# arduinoVisor2.net
KiCad netlist of a schematic drawn in EAGLE
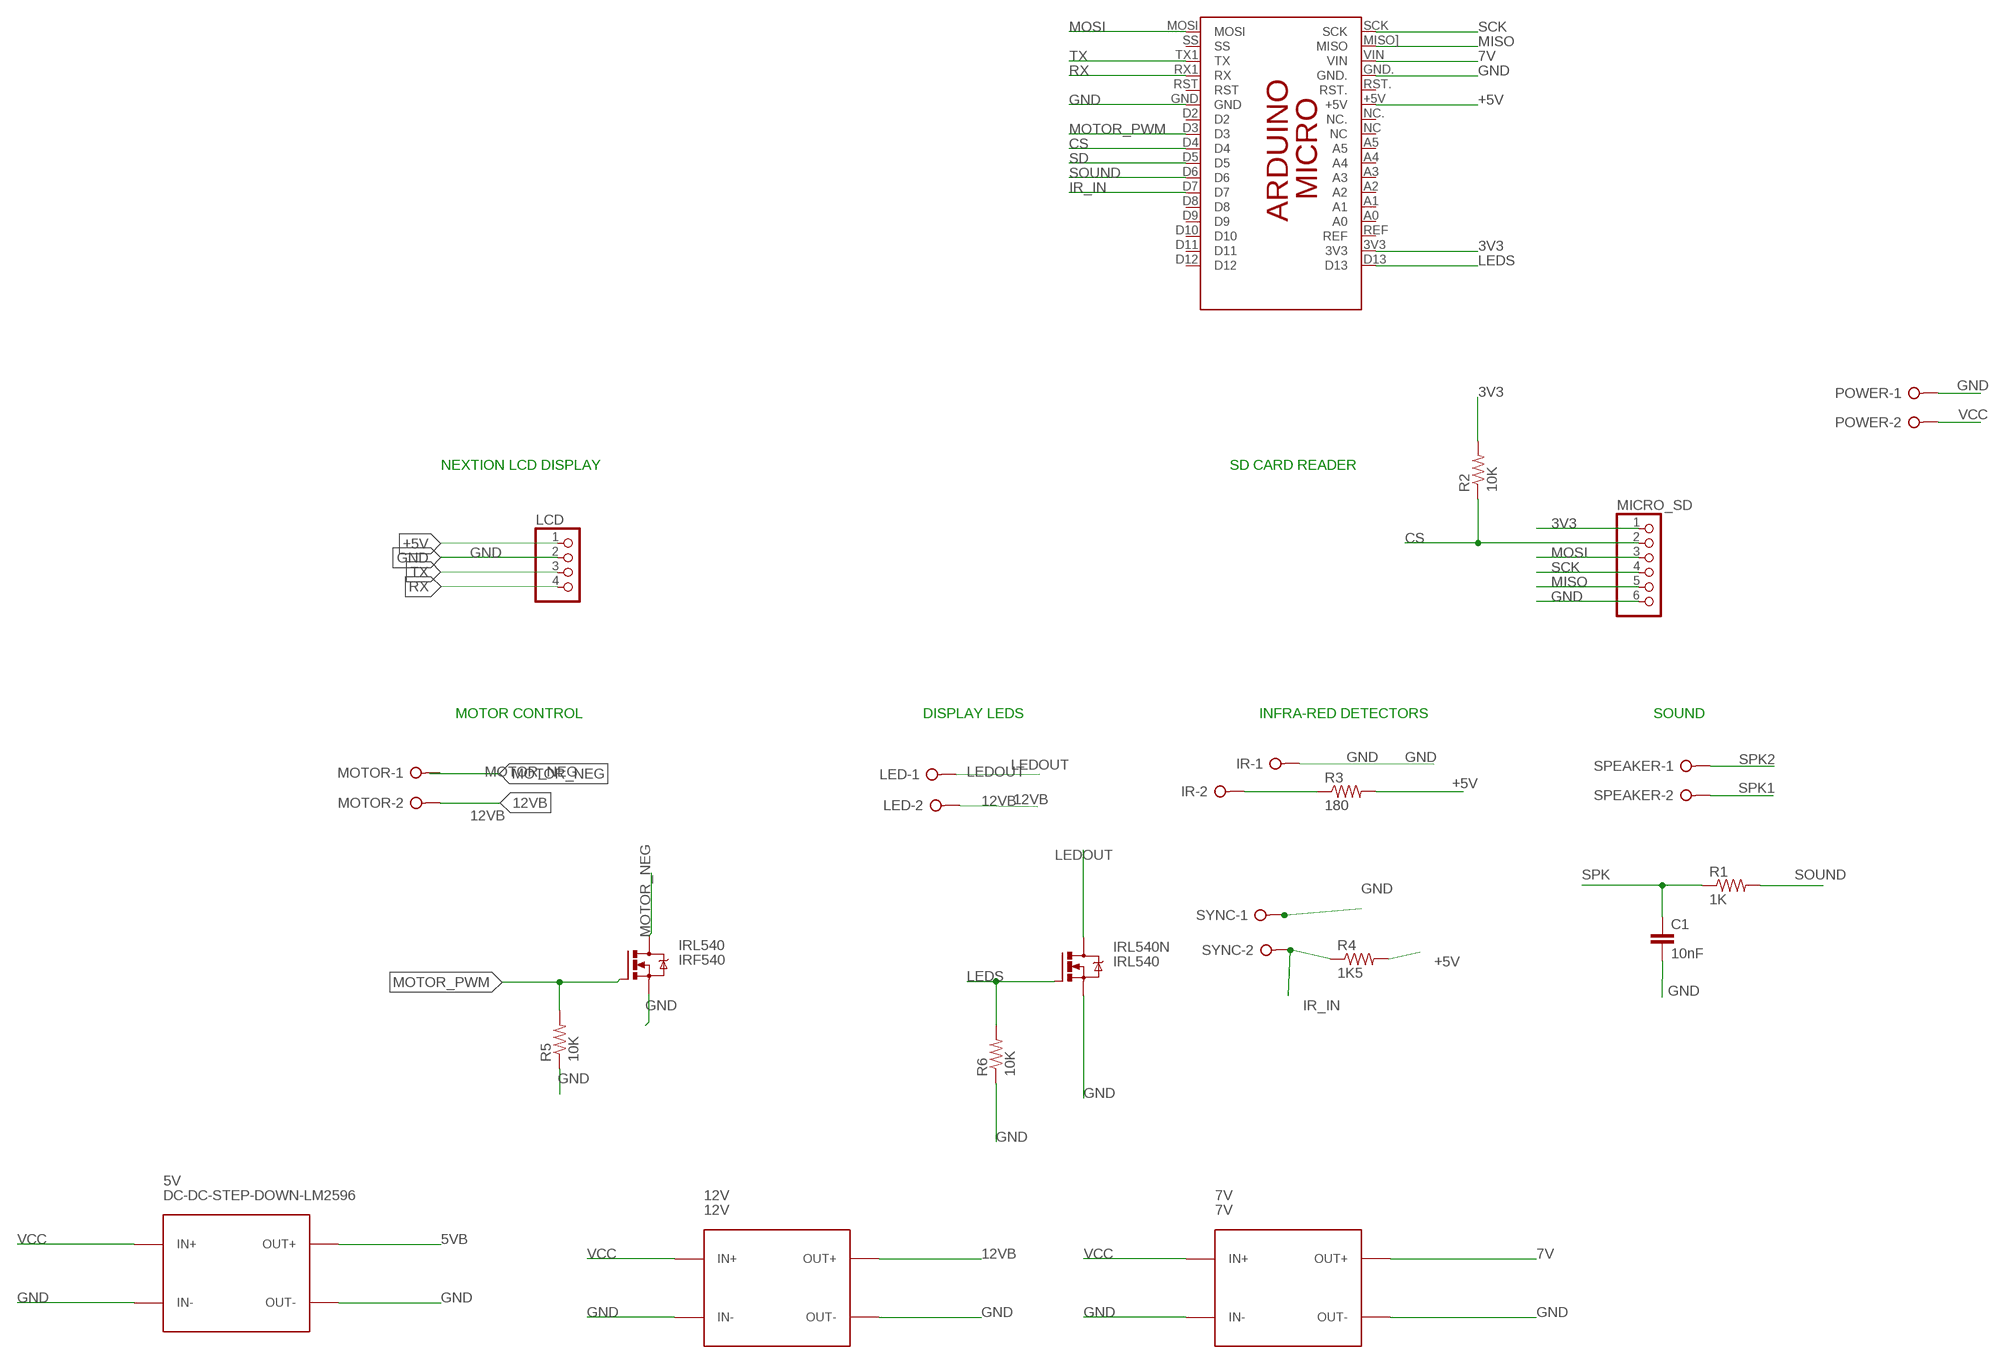
[diagram p0: schematic, sheet 1]
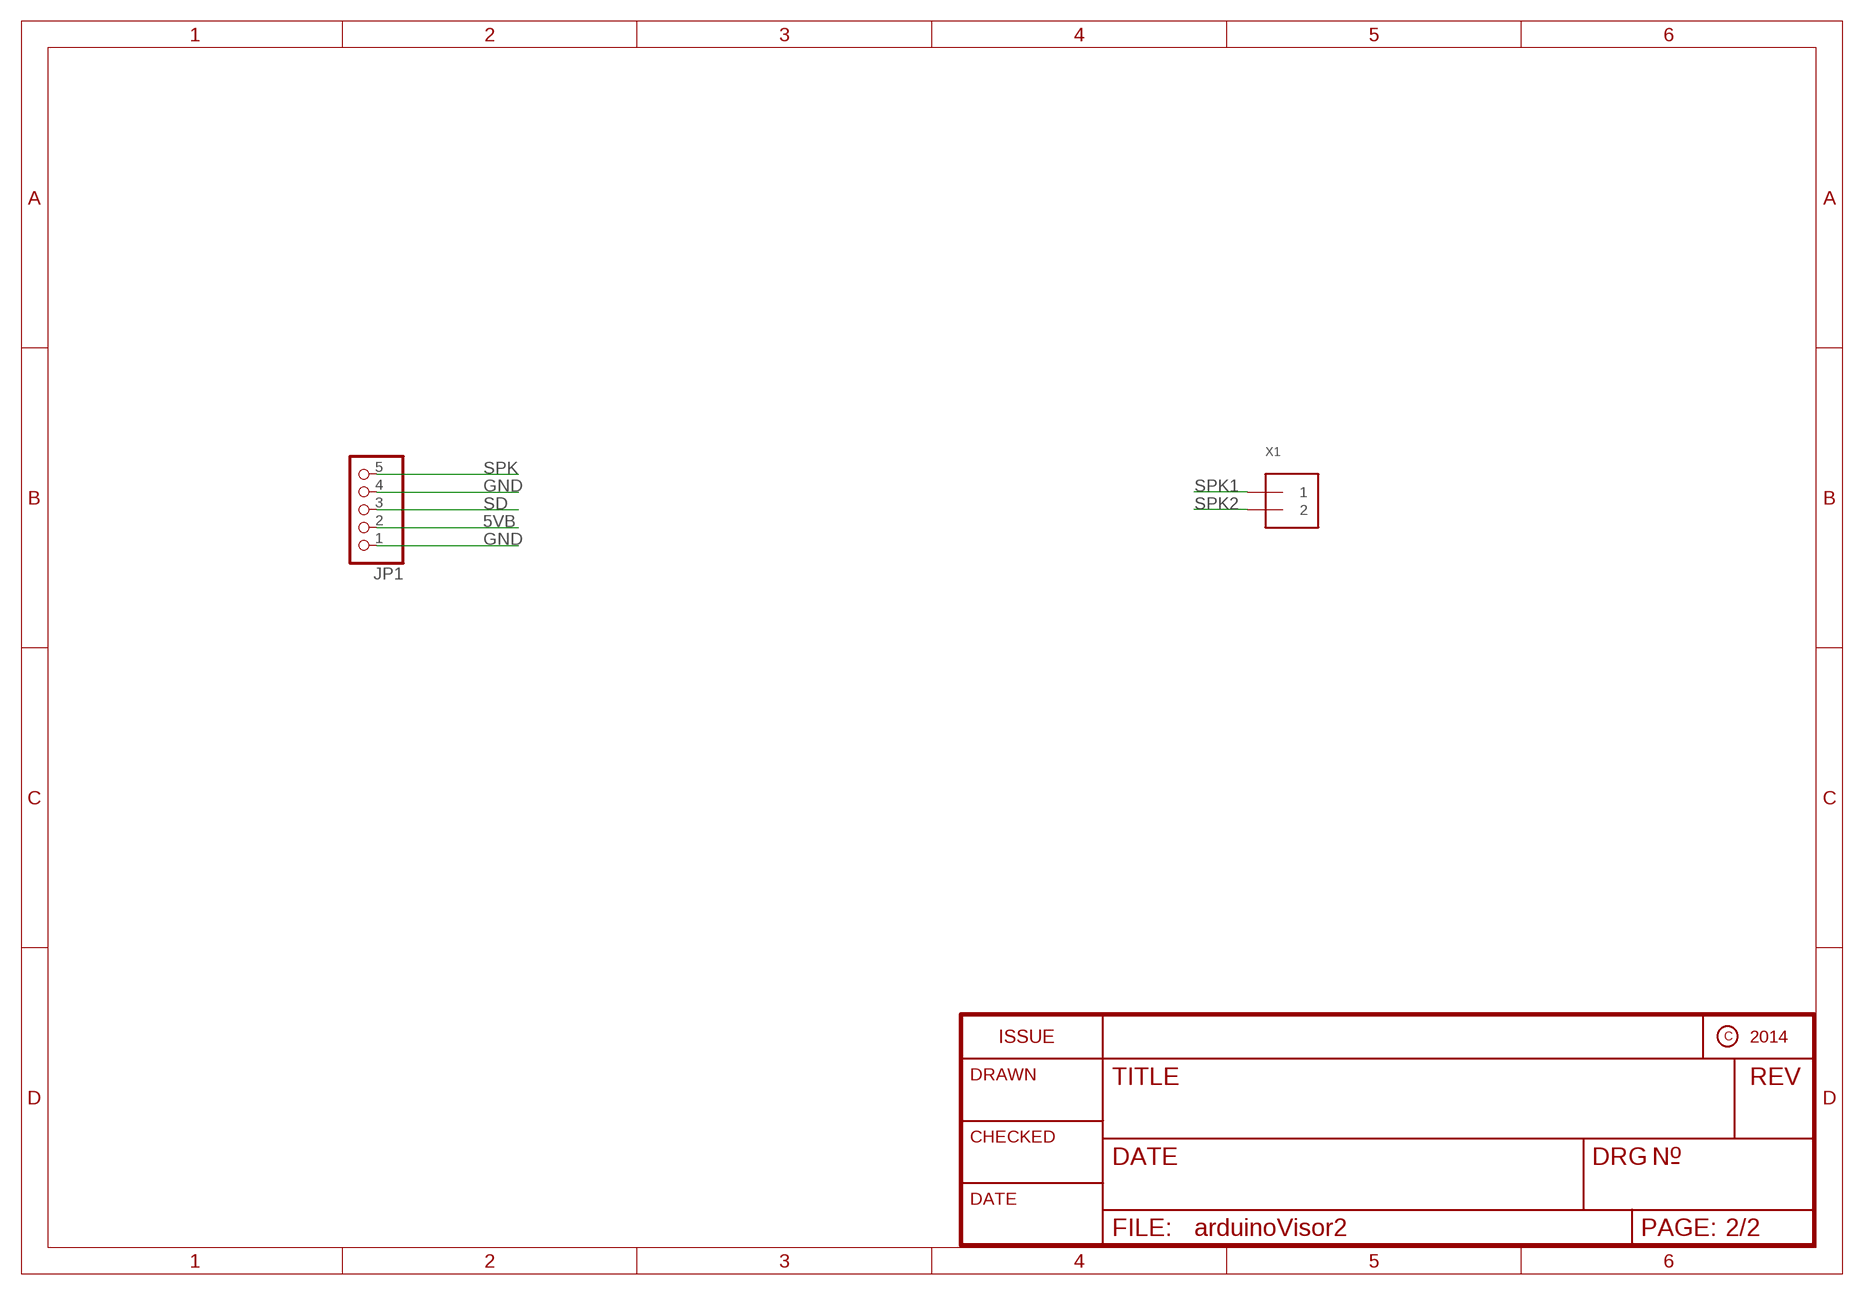
[diagram p1: schematic, sheet 2]

(export (version "E")
  (design (tool "Eeschema 10.0.6"))
  (components
    (comp (ref "5V")
      (value "DC-DC-STEP-DOWN-LM2596")
      (footprint "eagle-import:DC-DC-STEP-DOWN-LM2596")
      (libsource (lib "eagle-import") (part "DC-DC-STEP-DOWN-LM2596"))
    )
    (comp (ref "7V")
      (value "7V")
      (footprint "eagle-import:DC-DC-STEP-DOWN-LM2596")
      (libsource (lib "eagle-import") (part "DC-DC-STEP-DOWN-LM2596"))
    )
    (comp (ref "12V")
      (value "12V")
      (footprint "eagle-import:DC-DC-STEP-DOWN-LM2596")
      (libsource (lib "eagle-import") (part "DC-DC-STEP-DOWN-LM2596"))
    )
    (comp (ref "C1")
      (value "10nF")
      (footprint "eagle-import:C2.5-2")
      (libsource (lib "eagle-import") (part "C2.5/2"))
    )
    (comp (ref "IR")
      (value "W237-02P")
      (footprint "eagle-import:W237-132")
      (libsource (lib "eagle-import") (part "W237-02P"))
    )
    (comp (ref "IRL540")
      (value "IRF540")
      (footprint "eagle-import:TO220BV")
      (libsource (lib "eagle-import") (part "IRF540"))
    )
    (comp (ref "IRL540N")
      (value "IRL540")
      (footprint "eagle-import:TO220BV")
      (libsource (lib "eagle-import") (part "IRF540"))
    )
    (comp (ref "LCD")
      (value "PINHD-1X4")
      (footprint "eagle-import:1X04")
      (libsource (lib "eagle-import") (part "PINHD-1X4"))
    )
    (comp (ref "LED")
      (value "W237-02P")
      (footprint "eagle-import:W237-132")
      (libsource (lib "eagle-import") (part "W237-02P"))
    )
    (comp (ref "MICRO_SD")
      (value "PINHD-1X6")
      (footprint "eagle-import:1X06")
      (libsource (lib "eagle-import") (part "PINHD-1X6"))
    )
    (comp (ref "MOTOR")
      (value "W237-02P")
      (footprint "eagle-import:W237-132")
      (libsource (lib "eagle-import") (part "W237-02P"))
    )
    (comp (ref "PCB2")
      (value "ARDUINO_MICRO")
      (footprint "eagle-import:ARDUINO_MICRO")
      (libsource (lib "eagle-import") (part "ARDUINO_MICRO"))
    )
    (comp (ref "POWER")
      (value "W237-02P")
      (footprint "eagle-import:W237-132")
      (libsource (lib "eagle-import") (part "W237-02P"))
    )
    (comp (ref "R1")
      (value "1K")
      (footprint "eagle-import:0207_10")
      (libsource (lib "eagle-import") (part "R-US_0207/10"))
    )
    (comp (ref "R2")
      (value "10K")
      (footprint "eagle-import:0207_10")
      (libsource (lib "eagle-import") (part "R-US_0207/10"))
    )
    (comp (ref "R3")
      (value "180")
      (footprint "eagle-import:0207_10")
      (libsource (lib "eagle-import") (part "R-US_0207/10"))
    )
    (comp (ref "R4")
      (value "1K5")
      (footprint "eagle-import:0207_10")
      (libsource (lib "eagle-import") (part "R-US_0207/10"))
    )
    (comp (ref "R5")
      (value "10K")
      (footprint "eagle-import:0207_10")
      (libsource (lib "eagle-import") (part "R-US_0207/10"))
    )
    (comp (ref "R6")
      (value "10K")
      (footprint "eagle-import:0207_10")
      (libsource (lib "eagle-import") (part "R-US_0207/10"))
    )
    (comp (ref "SPEAKER")
      (value "W237-02P")
      (footprint "eagle-import:W237-132")
      (libsource (lib "eagle-import") (part "W237-02P"))
    )
    (comp (ref "SYNC")
      (value "W237-02P")
      (footprint "eagle-import:W237-132")
      (libsource (lib "eagle-import") (part "W237-02P"))
    )
    (comp (ref "JP1")
      (value "HEADER-1X570MIL")
      (footprint "eagle-import:1X05_ROUND_70")
      (libsource (lib "eagle-import") (part "HEADER-1X570MIL"))
    )
    (comp (ref "X1")
      (value "TERMBLOCK_1X2")
      (footprint "eagle-import:TERMBLOCK_1X2-3.5MM")
      (libsource (lib "eagle-import") (part "TERMBLOCK_1X2"))
    )
  )
  (nets
    (net (code "1") (name "+5V") (class "Default")
      (node (ref "LCD") (pin "1") (pinfunction "1_1") (pintype "passive"))
      (node (ref "PCB2") (pin "+5V") (pinfunction "+5V_+5V") (pintype "bidirectional"))
      (node (ref "R3") (pin "2") (pinfunction "2_2") (pintype "passive"))
      (node (ref "R4") (pin "2") (pinfunction "2_2") (pintype "passive"))
    )
    (net (code "2") (name "3V3") (class "Default")
      (node (ref "MICRO_SD") (pin "1") (pinfunction "1_1") (pintype "passive"))
      (node (ref "PCB2") (pin "3V3") (pinfunction "3V3_3V3") (pintype "bidirectional"))
      (node (ref "R2") (pin "2") (pinfunction "2_2") (pintype "passive"))
    )
    (net (code "3") (name "5VB") (class "Default")
      (node (ref "5V") (pin "OUT+") (pinfunction "OUT+_OUT+") (pintype "bidirectional"))
      (node (ref "JP1") (pin "2") (pinfunction "2_2") (pintype "passive"))
    )
    (net (code "4") (name "7V") (class "Default")
      (node (ref "7V") (pin "OUT+") (pinfunction "OUT+_OUT+") (pintype "bidirectional"))
      (node (ref "PCB2") (pin "VIN") (pinfunction "VIN_VIN") (pintype "bidirectional"))
    )
    (net (code "5") (name "12VB") (class "Default")
      (node (ref "12V") (pin "OUT+") (pinfunction "OUT+_OUT+") (pintype "bidirectional"))
      (node (ref "LED") (pin "2") (pinfunction "KL_2") (pintype "passive"))
      (node (ref "MOTOR") (pin "2") (pinfunction "KL_2") (pintype "passive"))
    )
    (net (code "6") (name "CS") (class "Default")
      (node (ref "MICRO_SD") (pin "2") (pinfunction "2_2") (pintype "passive"))
      (node (ref "PCB2") (pin "D4") (pinfunction "D4_D4") (pintype "bidirectional"))
      (node (ref "R2") (pin "1") (pinfunction "1_1") (pintype "passive"))
    )
    (net (code "7") (name "GND") (class "Default")
      (node (ref "12V") (pin "IN-") (pinfunction "IN-_IN-") (pintype "bidirectional"))
      (node (ref "12V") (pin "OUT-") (pinfunction "OUT-_OUT-") (pintype "bidirectional"))
      (node (ref "5V") (pin "IN-") (pinfunction "IN-_IN-") (pintype "bidirectional"))
      (node (ref "5V") (pin "OUT-") (pinfunction "OUT-_OUT-") (pintype "bidirectional"))
      (node (ref "7V") (pin "IN-") (pinfunction "IN-_IN-") (pintype "bidirectional"))
      (node (ref "7V") (pin "OUT-") (pinfunction "OUT-_OUT-") (pintype "bidirectional"))
      (node (ref "C1") (pin "2") (pinfunction "2_2") (pintype "passive"))
      (node (ref "IR") (pin "1") (pinfunction "KL_1") (pintype "passive"))
      (node (ref "IRL540") (pin "S") (pinfunction "S_S") (pintype "passive"))
      (node (ref "IRL540N") (pin "S") (pinfunction "S_S") (pintype "passive"))
      (node (ref "JP1") (pin "1") (pinfunction "1_1") (pintype "passive"))
      (node (ref "JP1") (pin "4") (pinfunction "4_4") (pintype "passive"))
      (node (ref "LCD") (pin "2") (pinfunction "2_2") (pintype "passive"))
      (node (ref "MICRO_SD") (pin "6") (pinfunction "6_6") (pintype "passive"))
      (node (ref "PCB2") (pin "GND") (pinfunction "GND_GND") (pintype "bidirectional"))
      (node (ref "PCB2") (pin "GND.") (pinfunction "GND._GND.") (pintype "bidirectional"))
      (node (ref "POWER") (pin "1") (pinfunction "KL_1") (pintype "passive"))
      (node (ref "R5") (pin "1") (pinfunction "1_1") (pintype "passive"))
      (node (ref "R6") (pin "1") (pinfunction "1_1") (pintype "passive"))
      (node (ref "SYNC") (pin "1") (pinfunction "KL_1") (pintype "passive"))
    )
    (net (code "8") (name "IR_IN") (class "Default")
      (node (ref "PCB2") (pin "D7") (pinfunction "D7_D7") (pintype "bidirectional"))
      (node (ref "R4") (pin "1") (pinfunction "1_1") (pintype "passive"))
      (node (ref "SYNC") (pin "2") (pinfunction "KL_2") (pintype "passive"))
    )
    (net (code "9") (name "LEDOUT") (class "Default")
      (node (ref "IRL540N") (pin "D") (pinfunction "D_D") (pintype "passive"))
      (node (ref "LED") (pin "1") (pinfunction "KL_1") (pintype "passive"))
    )
    (net (code "10") (name "LEDS") (class "Default")
      (node (ref "IRL540N") (pin "G") (pinfunction "G_G") (pintype "passive"))
      (node (ref "PCB2") (pin "D13") (pinfunction "D13_D13") (pintype "bidirectional"))
      (node (ref "R6") (pin "2") (pinfunction "2_2") (pintype "passive"))
    )
    (net (code "11") (name "MISO") (class "Default")
      (node (ref "MICRO_SD") (pin "5") (pinfunction "5_5") (pintype "passive"))
      (node (ref "PCB2") (pin "MISO]") (pinfunction "MISO_MISO]") (pintype "bidirectional"))
    )
    (net (code "12") (name "MOSI") (class "Default")
      (node (ref "MICRO_SD") (pin "3") (pinfunction "3_3") (pintype "passive"))
      (node (ref "PCB2") (pin "MOSI") (pinfunction "MOSI_MOSI") (pintype "bidirectional"))
    )
    (net (code "13") (name "MOTOR_NEG") (class "Default")
      (node (ref "IRL540") (pin "D") (pinfunction "D_D") (pintype "passive"))
      (node (ref "MOTOR") (pin "1") (pinfunction "KL_1") (pintype "passive"))
    )
    (net (code "14") (name "MOTOR_PWM") (class "Default")
      (node (ref "IRL540") (pin "G") (pinfunction "G_G") (pintype "passive"))
      (node (ref "PCB2") (pin "D3") (pinfunction "D3_D3") (pintype "bidirectional"))
      (node (ref "R5") (pin "2") (pinfunction "2_2") (pintype "passive"))
    )
    (net (code "15") (name "Net-(IRB-KL)") (class "Default")
      (node (ref "IR") (pin "2") (pinfunction "KL_2") (pintype "passive"))
      (node (ref "R3") (pin "1") (pinfunction "1_1") (pintype "passive"))
    )
    (net (code "16") (name "RX") (class "Default")
      (node (ref "LCD") (pin "4") (pinfunction "4_4") (pintype "passive"))
      (node (ref "PCB2") (pin "RX1") (pinfunction "RX_RX1") (pintype "bidirectional"))
    )
    (net (code "17") (name "SCK") (class "Default")
      (node (ref "MICRO_SD") (pin "4") (pinfunction "4_4") (pintype "passive"))
      (node (ref "PCB2") (pin "SCK") (pinfunction "SCK_SCK") (pintype "bidirectional"))
    )
    (net (code "18") (name "SD") (class "Default")
      (node (ref "JP1") (pin "3") (pinfunction "3_3") (pintype "passive"))
      (node (ref "PCB2") (pin "D5") (pinfunction "D5_D5") (pintype "bidirectional"))
    )
    (net (code "19") (name "SOUND") (class "Default")
      (node (ref "PCB2") (pin "D6") (pinfunction "D6_D6") (pintype "bidirectional"))
      (node (ref "R1") (pin "2") (pinfunction "2_2") (pintype "passive"))
    )
    (net (code "20") (name "SPK") (class "Default")
      (node (ref "C1") (pin "1") (pinfunction "1_1") (pintype "passive"))
      (node (ref "JP1") (pin "5") (pinfunction "5_5") (pintype "passive"))
      (node (ref "R1") (pin "1") (pinfunction "1_1") (pintype "passive"))
    )
    (net (code "21") (name "SPK1") (class "Default")
      (node (ref "SPEAKER") (pin "2") (pinfunction "KL_2") (pintype "passive"))
      (node (ref "X1") (pin "1") (pinfunction "1_1") (pintype "passive"))
    )
    (net (code "22") (name "SPK2") (class "Default")
      (node (ref "SPEAKER") (pin "1") (pinfunction "KL_1") (pintype "passive"))
      (node (ref "X1") (pin "2") (pinfunction "2_2") (pintype "passive"))
    )
    (net (code "23") (name "TX") (class "Default")
      (node (ref "LCD") (pin "3") (pinfunction "3_3") (pintype "passive"))
      (node (ref "PCB2") (pin "TX1") (pinfunction "TX_TX1") (pintype "bidirectional"))
    )
    (net (code "24") (name "VCC") (class "Default")
      (node (ref "12V") (pin "IN+") (pinfunction "IN+_IN+") (pintype "bidirectional"))
      (node (ref "5V") (pin "IN+") (pinfunction "IN+_IN+") (pintype "bidirectional"))
      (node (ref "7V") (pin "IN+") (pinfunction "IN+_IN+") (pintype "bidirectional"))
      (node (ref "POWER") (pin "2") (pinfunction "KL_2") (pintype "passive"))
    )
    (net (code "25") (name "unconnected-(PCB2-PadA0)") (class "Default")
      (node (ref "PCB2") (pin "A0") (pinfunction "A0_A0") (pintype "bidirectional"))
    )
    (net (code "26") (name "unconnected-(PCB2-PadA1)") (class "Default")
      (node (ref "PCB2") (pin "A1") (pinfunction "A1_A1") (pintype "bidirectional"))
    )
    (net (code "27") (name "unconnected-(PCB2-PadA2)") (class "Default")
      (node (ref "PCB2") (pin "A2") (pinfunction "A2_A2") (pintype "bidirectional"))
    )
    (net (code "28") (name "unconnected-(PCB2-PadA3)") (class "Default")
      (node (ref "PCB2") (pin "A3") (pinfunction "A3_A3") (pintype "bidirectional"))
    )
    (net (code "29") (name "unconnected-(PCB2-PadA4)") (class "Default")
      (node (ref "PCB2") (pin "A4") (pinfunction "A4_A4") (pintype "bidirectional"))
    )
    (net (code "30") (name "unconnected-(PCB2-PadA5)") (class "Default")
      (node (ref "PCB2") (pin "A5") (pinfunction "A5_A5") (pintype "bidirectional"))
    )
    (net (code "31") (name "unconnected-(PCB2-PadD2)") (class "Default")
      (node (ref "PCB2") (pin "D2") (pinfunction "D2_D2") (pintype "bidirectional"))
    )
    (net (code "32") (name "unconnected-(PCB2-PadD8)") (class "Default")
      (node (ref "PCB2") (pin "D8") (pinfunction "D8_D8") (pintype "bidirectional"))
    )
    (net (code "33") (name "unconnected-(PCB2-PadD9)") (class "Default")
      (node (ref "PCB2") (pin "D9") (pinfunction "D9_D9") (pintype "bidirectional"))
    )
    (net (code "34") (name "unconnected-(PCB2-PadD10)") (class "Default")
      (node (ref "PCB2") (pin "D10") (pinfunction "D10_D10") (pintype "bidirectional"))
    )
    (net (code "35") (name "unconnected-(PCB2-PadD11)") (class "Default")
      (node (ref "PCB2") (pin "D11") (pinfunction "D11_D11") (pintype "bidirectional"))
    )
    (net (code "36") (name "unconnected-(PCB2-PadD12)") (class "Default")
      (node (ref "PCB2") (pin "D12") (pinfunction "D12_D12") (pintype "bidirectional"))
    )
    (net (code "37") (name "unconnected-(PCB2-PadNC)") (class "Default")
      (node (ref "PCB2") (pin "NC") (pinfunction "NC_NC") (pintype "bidirectional"))
    )
    (net (code "38") (name "unconnected-(PCB2-PadNC.)") (class "Default")
      (node (ref "PCB2") (pin "NC.") (pinfunction "NC._NC.") (pintype "bidirectional"))
    )
    (net (code "39") (name "unconnected-(PCB2-PadREF)") (class "Default")
      (node (ref "PCB2") (pin "REF") (pinfunction "REF_REF") (pintype "bidirectional"))
    )
    (net (code "40") (name "unconnected-(PCB2-PadRST)") (class "Default")
      (node (ref "PCB2") (pin "RST") (pinfunction "RST_RST") (pintype "bidirectional"))
    )
    (net (code "41") (name "unconnected-(PCB2-PadRST.)") (class "Default")
      (node (ref "PCB2") (pin "RST.") (pinfunction "RST._RST.") (pintype "bidirectional"))
    )
    (net (code "42") (name "unconnected-(PCB2-PadSS)") (class "Default")
      (node (ref "PCB2") (pin "SS") (pinfunction "SS_SS") (pintype "bidirectional"))
    )
  )
)
